# Peripherials.net
KiCad netlist of a schematic drawn in Altium Designer
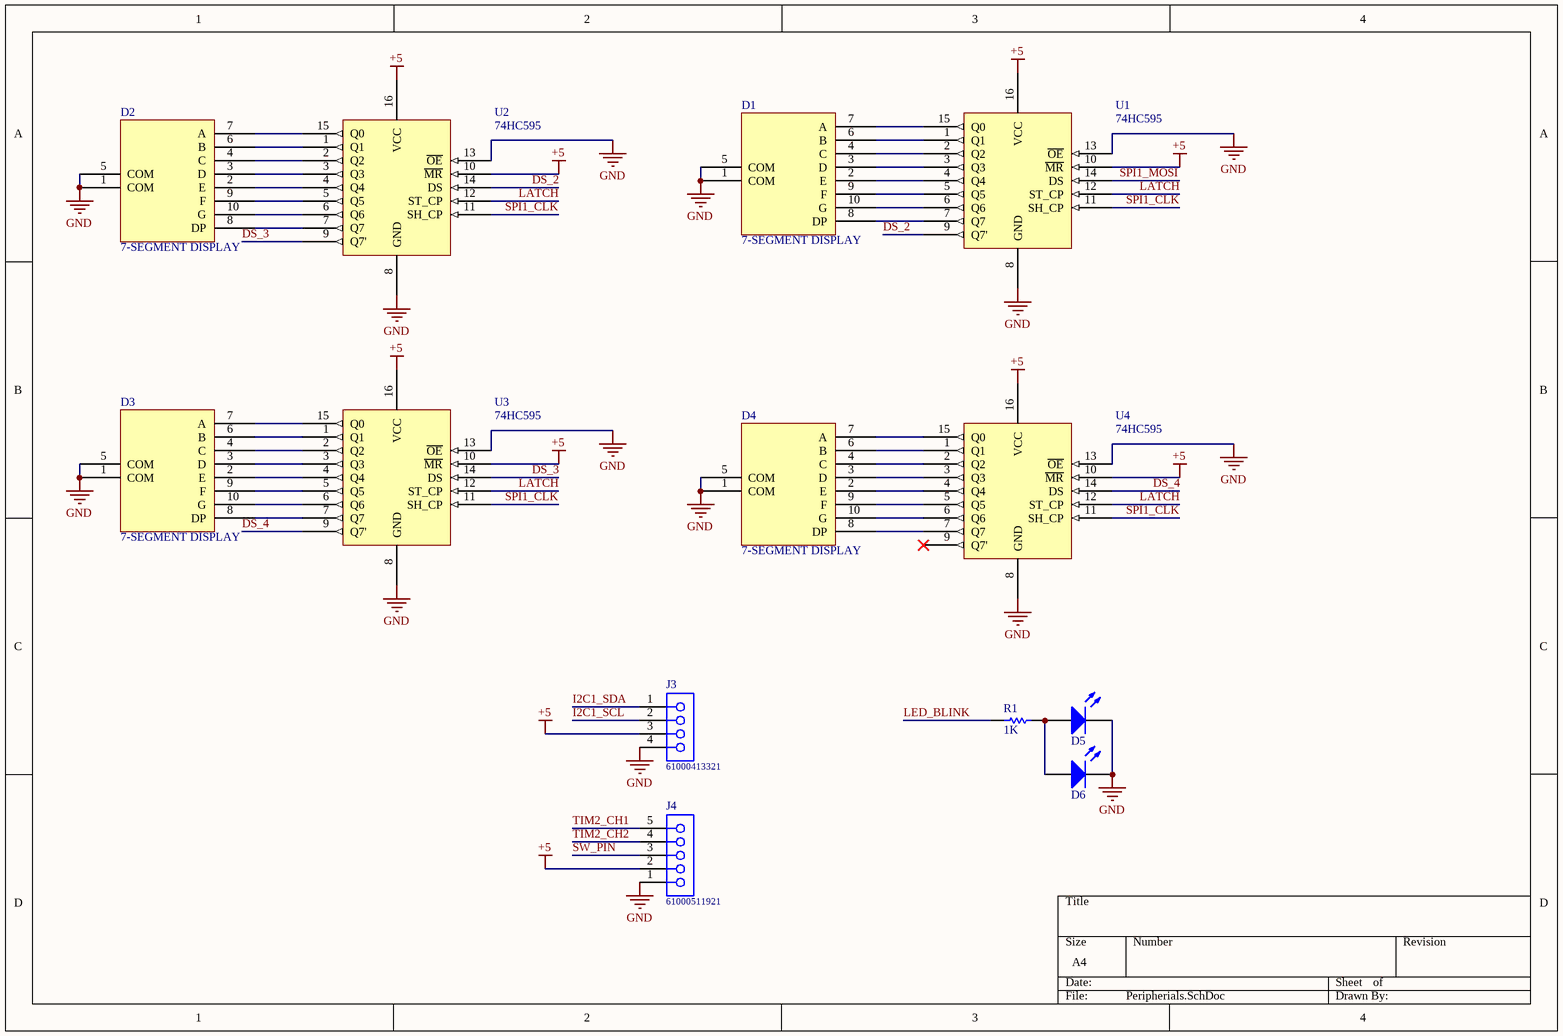
[diagram p0: Peripherials.SchDoc]

(export (version "E")
  (design (tool "Eeschema 10.0.6"))
  (components
    (comp (ref "D1")
      (value "7-SEGMENT DISPLAY")
      (footprint "7-SEGMENT 1.8INCH")
      (libsource (lib "Giang's Libs") (part "7-SEGMENT"))
    )
    (comp (ref "D2")
      (value "7-SEGMENT DISPLAY")
      (footprint "7-SEGMENT 1.8INCH")
      (libsource (lib "Giang's Libs") (part "7-SEGMENT"))
    )
    (comp (ref "D3")
      (value "7-SEGMENT DISPLAY")
      (footprint "7-SEGMENT 1.8INCH")
      (libsource (lib "Giang's Libs") (part "7-SEGMENT"))
    )
    (comp (ref "D4")
      (value "7-SEGMENT DISPLAY")
      (footprint "7-SEGMENT 1.8INCH")
      (libsource (lib "Giang's Libs") (part "7-SEGMENT"))
    )
    (comp (ref "D5") (value "LED") (footprint "LED-3mm") (libsource (lib "PIF_Library") (part "LED")))
    (comp (ref "D6") (value "LED") (footprint "LED-3mm") (libsource (lib "PIF_Library") (part "LED")))
    (comp (ref "J3")
      (value "61000413321")
      (footprint "61000413321")
      (description "WR-PHD Socket Header, SMT, pitch 2.54mm, Single Row, Vertical, 4p")
      (fields (field (name "MANUFACTURER") "Wurth Elektronik"))
      (libsource (lib "Altium_WR-PHD (rev20a)") (part "61000413321"))
    )
    (comp (ref "J4")
      (value "61000511921")
      (footprint "61000511921")
      (description "WR-PHD Socket Header, SMT, pitch 2.54mm, Single Row, Vertical, 5p")
      (fields (field (name "MANUFACTURER") "Wurth Elektronik"))
      (libsource (lib "Altium_WR-PHD (rev20a)") (part "61000511921"))
    )
    (comp (ref "R1")
      (value "1K")
      (footprint "RES-SM-0805")
      (description "Resistor")
      (fields (field (name "Comment") "RESISTOR SMD"))
      (libsource (lib "PIF_Library") (part "RESISTOR SMD"))
    )
    (comp (ref "U1")
      (value "74HC595")
      (footprint "SOIC-16")
      (description "8-Bit Serial-Input/Serial orParallel-Output ShiftRegister with Latched3-State Outputs")
      (libsource (lib "Giang's Libs") (part "74HC595"))
    )
    (comp (ref "U2")
      (value "74HC595")
      (footprint "SOIC-16")
      (description "8-Bit Serial-Input/Serial orParallel-Output ShiftRegister with Latched3-State Outputs")
      (libsource (lib "Giang's Libs") (part "74HC595"))
    )
    (comp (ref "U3")
      (value "74HC595")
      (footprint "SOIC-16")
      (description "8-Bit Serial-Input/Serial orParallel-Output ShiftRegister with Latched3-State Outputs")
      (libsource (lib "Giang's Libs") (part "74HC595"))
    )
    (comp (ref "U4")
      (value "74HC595")
      (footprint "SOIC-16")
      (description "8-Bit Serial-Input/Serial orParallel-Output ShiftRegister with Latched3-State Outputs")
      (libsource (lib "Giang's Libs") (part "74HC595"))
    )
  )
  (nets
    (net (code "1") (name "+5") (class "Default")
      (node (ref "J3") (pin "3") (pinfunction "3_3") (pintype "passive"))
      (node (ref "J4") (pin "2") (pinfunction "2_2") (pintype "passive"))
      (node (ref "U1") (pin "10") (pinfunction "~{MR}_10") (pintype "input"))
      (node (ref "U1") (pin "16") (pinfunction "VCC_16") (pintype "power_in"))
      (node (ref "U2") (pin "10") (pinfunction "~{MR}_10") (pintype "input"))
      (node (ref "U2") (pin "16") (pinfunction "VCC_16") (pintype "power_in"))
      (node (ref "U3") (pin "10") (pinfunction "~{MR}_10") (pintype "input"))
      (node (ref "U3") (pin "16") (pinfunction "VCC_16") (pintype "power_in"))
      (node (ref "U4") (pin "10") (pinfunction "~{MR}_10") (pintype "input"))
      (node (ref "U4") (pin "16") (pinfunction "VCC_16") (pintype "power_in"))
    )
    (net (code "2") (name "/DS_2") (class "Default")
      (node (ref "U1") (pin "9") (pinfunction "Q7'_9") (pintype "output"))
      (node (ref "U2") (pin "14") (pinfunction "DS_14") (pintype "input"))
    )
    (net (code "3") (name "/DS_3") (class "Default")
      (node (ref "U2") (pin "9") (pinfunction "Q7'_9") (pintype "output"))
      (node (ref "U3") (pin "14") (pinfunction "DS_14") (pintype "input"))
    )
    (net (code "4") (name "/DS_4") (class "Default")
      (node (ref "U3") (pin "9") (pinfunction "Q7'_9") (pintype "output"))
      (node (ref "U4") (pin "14") (pinfunction "DS_14") (pintype "input"))
    )
    (net (code "5") (name "/I2C1_SCL") (class "Default")
      (node (ref "J3") (pin "2") (pinfunction "2_2") (pintype "passive"))
    )
    (net (code "6") (name "/I2C1_SDA") (class "Default")
      (node (ref "J3") (pin "1") (pinfunction "1_1") (pintype "passive"))
    )
    (net (code "7") (name "/LATCH") (class "Default")
      (node (ref "U1") (pin "12") (pinfunction "ST_CP_12") (pintype "input"))
      (node (ref "U2") (pin "12") (pinfunction "ST_CP_12") (pintype "input"))
      (node (ref "U3") (pin "12") (pinfunction "ST_CP_12") (pintype "input"))
      (node (ref "U4") (pin "12") (pinfunction "ST_CP_12") (pintype "input"))
    )
    (net (code "8") (name "/LED_BLINK") (class "Default")
      (node (ref "R1") (pin "1") (pinfunction "1_1") (pintype "passive"))
    )
    (net (code "9") (name "/SPI1_CLK") (class "Default")
      (node (ref "U1") (pin "11") (pinfunction "SH_CP_11") (pintype "input"))
      (node (ref "U2") (pin "11") (pinfunction "SH_CP_11") (pintype "input"))
      (node (ref "U3") (pin "11") (pinfunction "SH_CP_11") (pintype "input"))
      (node (ref "U4") (pin "11") (pinfunction "SH_CP_11") (pintype "input"))
    )
    (net (code "10") (name "/SPI1_MOSI") (class "Default")
      (node (ref "U1") (pin "14") (pinfunction "DS_14") (pintype "input"))
    )
    (net (code "11") (name "/SW_PIN") (class "Default")
      (node (ref "J4") (pin "3") (pinfunction "3_3") (pintype "passive"))
    )
    (net (code "12") (name "/TIM2_CH1") (class "Default")
      (node (ref "J4") (pin "5") (pinfunction "5_5") (pintype "passive"))
    )
    (net (code "13") (name "/TIM2_CH2") (class "Default")
      (node (ref "J4") (pin "4") (pinfunction "4_4") (pintype "passive"))
    )
    (net (code "14") (name "GND") (class "Default")
      (node (ref "D1") (pin "1") (pinfunction "COM_1") (pintype "passive"))
      (node (ref "D1") (pin "5") (pinfunction "COM_5") (pintype "passive"))
      (node (ref "D2") (pin "1") (pinfunction "COM_1") (pintype "passive"))
      (node (ref "D2") (pin "5") (pinfunction "COM_5") (pintype "passive"))
      (node (ref "D3") (pin "1") (pinfunction "COM_1") (pintype "passive"))
      (node (ref "D3") (pin "5") (pinfunction "COM_5") (pintype "passive"))
      (node (ref "D4") (pin "1") (pinfunction "COM_1") (pintype "passive"))
      (node (ref "D4") (pin "5") (pinfunction "COM_5") (pintype "passive"))
      (node (ref "D5") (pin "2") (pinfunction "K_2") (pintype "passive"))
      (node (ref "D6") (pin "2") (pinfunction "K_2") (pintype "passive"))
      (node (ref "J3") (pin "4") (pinfunction "4_4") (pintype "passive"))
      (node (ref "J4") (pin "1") (pinfunction "1_1") (pintype "passive"))
      (node (ref "U1") (pin "13") (pinfunction "~{OE}_13") (pintype "input"))
      (node (ref "U1") (pin "8") (pinfunction "GND_8") (pintype "power_in"))
      (node (ref "U2") (pin "13") (pinfunction "~{OE}_13") (pintype "input"))
      (node (ref "U2") (pin "8") (pinfunction "GND_8") (pintype "power_in"))
      (node (ref "U3") (pin "13") (pinfunction "~{OE}_13") (pintype "input"))
      (node (ref "U3") (pin "8") (pinfunction "GND_8") (pintype "power_in"))
      (node (ref "U4") (pin "13") (pinfunction "~{OE}_13") (pintype "input"))
      (node (ref "U4") (pin "8") (pinfunction "GND_8") (pintype "power_in"))
    )
    (net (code "15") (name "Net-(D1-A)") (class "Default")
      (node (ref "D1") (pin "7") (pinfunction "A_7") (pintype "passive"))
      (node (ref "U1") (pin "15") (pinfunction "Q0_15") (pintype "output"))
    )
    (net (code "16") (name "Net-(D1-B)") (class "Default")
      (node (ref "D1") (pin "6") (pinfunction "B_6") (pintype "passive"))
      (node (ref "U1") (pin "1") (pinfunction "Q1_1") (pintype "output"))
    )
    (net (code "17") (name "Net-(D1-C)") (class "Default")
      (node (ref "D1") (pin "4") (pinfunction "C_4") (pintype "passive"))
      (node (ref "U1") (pin "2") (pinfunction "Q2_2") (pintype "output"))
    )
    (net (code "18") (name "Net-(D1-D)") (class "Default")
      (node (ref "D1") (pin "3") (pinfunction "D_3") (pintype "passive"))
      (node (ref "U1") (pin "3") (pinfunction "Q3_3") (pintype "output"))
    )
    (net (code "19") (name "Net-(D1-DP)") (class "Default")
      (node (ref "D1") (pin "8") (pinfunction "DP_8") (pintype "passive"))
      (node (ref "U1") (pin "7") (pinfunction "Q7_7") (pintype "output"))
    )
    (net (code "20") (name "Net-(D1-E)") (class "Default")
      (node (ref "D1") (pin "2") (pinfunction "E_2") (pintype "passive"))
      (node (ref "U1") (pin "4") (pinfunction "Q4_4") (pintype "output"))
    )
    (net (code "21") (name "Net-(D1-F)") (class "Default")
      (node (ref "D1") (pin "9") (pinfunction "F_9") (pintype "passive"))
      (node (ref "U1") (pin "5") (pinfunction "Q5_5") (pintype "output"))
    )
    (net (code "22") (name "Net-(D1-G)") (class "Default")
      (node (ref "D1") (pin "10") (pinfunction "G_10") (pintype "passive"))
      (node (ref "U1") (pin "6") (pinfunction "Q6_6") (pintype "output"))
    )
    (net (code "23") (name "Net-(D2-A)") (class "Default")
      (node (ref "D2") (pin "7") (pinfunction "A_7") (pintype "passive"))
      (node (ref "U2") (pin "15") (pinfunction "Q0_15") (pintype "output"))
    )
    (net (code "24") (name "Net-(D2-B)") (class "Default")
      (node (ref "D2") (pin "6") (pinfunction "B_6") (pintype "passive"))
      (node (ref "U2") (pin "1") (pinfunction "Q1_1") (pintype "output"))
    )
    (net (code "25") (name "Net-(D2-C)") (class "Default")
      (node (ref "D2") (pin "4") (pinfunction "C_4") (pintype "passive"))
      (node (ref "U2") (pin "2") (pinfunction "Q2_2") (pintype "output"))
    )
    (net (code "26") (name "Net-(D2-D)") (class "Default")
      (node (ref "D2") (pin "3") (pinfunction "D_3") (pintype "passive"))
      (node (ref "U2") (pin "3") (pinfunction "Q3_3") (pintype "output"))
    )
    (net (code "27") (name "Net-(D2-DP)") (class "Default")
      (node (ref "D2") (pin "8") (pinfunction "DP_8") (pintype "passive"))
      (node (ref "U2") (pin "7") (pinfunction "Q7_7") (pintype "output"))
    )
    (net (code "28") (name "Net-(D2-E)") (class "Default")
      (node (ref "D2") (pin "2") (pinfunction "E_2") (pintype "passive"))
      (node (ref "U2") (pin "4") (pinfunction "Q4_4") (pintype "output"))
    )
    (net (code "29") (name "Net-(D2-F)") (class "Default")
      (node (ref "D2") (pin "9") (pinfunction "F_9") (pintype "passive"))
      (node (ref "U2") (pin "5") (pinfunction "Q5_5") (pintype "output"))
    )
    (net (code "30") (name "Net-(D2-G)") (class "Default")
      (node (ref "D2") (pin "10") (pinfunction "G_10") (pintype "passive"))
      (node (ref "U2") (pin "6") (pinfunction "Q6_6") (pintype "output"))
    )
    (net (code "31") (name "Net-(D3-A)") (class "Default")
      (node (ref "D3") (pin "7") (pinfunction "A_7") (pintype "passive"))
      (node (ref "U3") (pin "15") (pinfunction "Q0_15") (pintype "output"))
    )
    (net (code "32") (name "Net-(D3-B)") (class "Default")
      (node (ref "D3") (pin "6") (pinfunction "B_6") (pintype "passive"))
      (node (ref "U3") (pin "1") (pinfunction "Q1_1") (pintype "output"))
    )
    (net (code "33") (name "Net-(D3-C)") (class "Default")
      (node (ref "D3") (pin "4") (pinfunction "C_4") (pintype "passive"))
      (node (ref "U3") (pin "2") (pinfunction "Q2_2") (pintype "output"))
    )
    (net (code "34") (name "Net-(D3-D)") (class "Default")
      (node (ref "D3") (pin "3") (pinfunction "D_3") (pintype "passive"))
      (node (ref "U3") (pin "3") (pinfunction "Q3_3") (pintype "output"))
    )
    (net (code "35") (name "Net-(D3-DP)") (class "Default")
      (node (ref "D3") (pin "8") (pinfunction "DP_8") (pintype "passive"))
      (node (ref "U3") (pin "7") (pinfunction "Q7_7") (pintype "output"))
    )
    (net (code "36") (name "Net-(D3-E)") (class "Default")
      (node (ref "D3") (pin "2") (pinfunction "E_2") (pintype "passive"))
      (node (ref "U3") (pin "4") (pinfunction "Q4_4") (pintype "output"))
    )
    (net (code "37") (name "Net-(D3-F)") (class "Default")
      (node (ref "D3") (pin "9") (pinfunction "F_9") (pintype "passive"))
      (node (ref "U3") (pin "5") (pinfunction "Q5_5") (pintype "output"))
    )
    (net (code "38") (name "Net-(D3-G)") (class "Default")
      (node (ref "D3") (pin "10") (pinfunction "G_10") (pintype "passive"))
      (node (ref "U3") (pin "6") (pinfunction "Q6_6") (pintype "output"))
    )
    (net (code "39") (name "Net-(D4-A)") (class "Default")
      (node (ref "D4") (pin "7") (pinfunction "A_7") (pintype "passive"))
      (node (ref "U4") (pin "15") (pinfunction "Q0_15") (pintype "output"))
    )
    (net (code "40") (name "Net-(D4-B)") (class "Default")
      (node (ref "D4") (pin "6") (pinfunction "B_6") (pintype "passive"))
      (node (ref "U4") (pin "1") (pinfunction "Q1_1") (pintype "output"))
    )
    (net (code "41") (name "Net-(D4-C)") (class "Default")
      (node (ref "D4") (pin "4") (pinfunction "C_4") (pintype "passive"))
      (node (ref "U4") (pin "2") (pinfunction "Q2_2") (pintype "output"))
    )
    (net (code "42") (name "Net-(D4-D)") (class "Default")
      (node (ref "D4") (pin "3") (pinfunction "D_3") (pintype "passive"))
      (node (ref "U4") (pin "3") (pinfunction "Q3_3") (pintype "output"))
    )
    (net (code "43") (name "Net-(D4-DP)") (class "Default")
      (node (ref "D4") (pin "8") (pinfunction "DP_8") (pintype "passive"))
      (node (ref "U4") (pin "7") (pinfunction "Q7_7") (pintype "output"))
    )
    (net (code "44") (name "Net-(D4-E)") (class "Default")
      (node (ref "D4") (pin "2") (pinfunction "E_2") (pintype "passive"))
      (node (ref "U4") (pin "4") (pinfunction "Q4_4") (pintype "output"))
    )
    (net (code "45") (name "Net-(D4-F)") (class "Default")
      (node (ref "D4") (pin "9") (pinfunction "F_9") (pintype "passive"))
      (node (ref "U4") (pin "5") (pinfunction "Q5_5") (pintype "output"))
    )
    (net (code "46") (name "Net-(D4-G)") (class "Default")
      (node (ref "D4") (pin "10") (pinfunction "G_10") (pintype "passive"))
      (node (ref "U4") (pin "6") (pinfunction "Q6_6") (pintype "output"))
    )
    (net (code "47") (name "Net-(D5-A)") (class "Default")
      (node (ref "D5") (pin "1") (pinfunction "A_1") (pintype "passive"))
      (node (ref "D6") (pin "1") (pinfunction "A_1") (pintype "passive"))
      (node (ref "R1") (pin "2") (pinfunction "2_2") (pintype "passive"))
    )
    (net (code "48") (name "unconnected-(U4-Q7'-Pad9)") (class "Default")
      (node (ref "U4") (pin "9") (pinfunction "Q7'_9") (pintype "output+no_connect"))
    )
  )
)
